# NodeSensor.net
KiCad netlist of a schematic drawn in Altium Designer
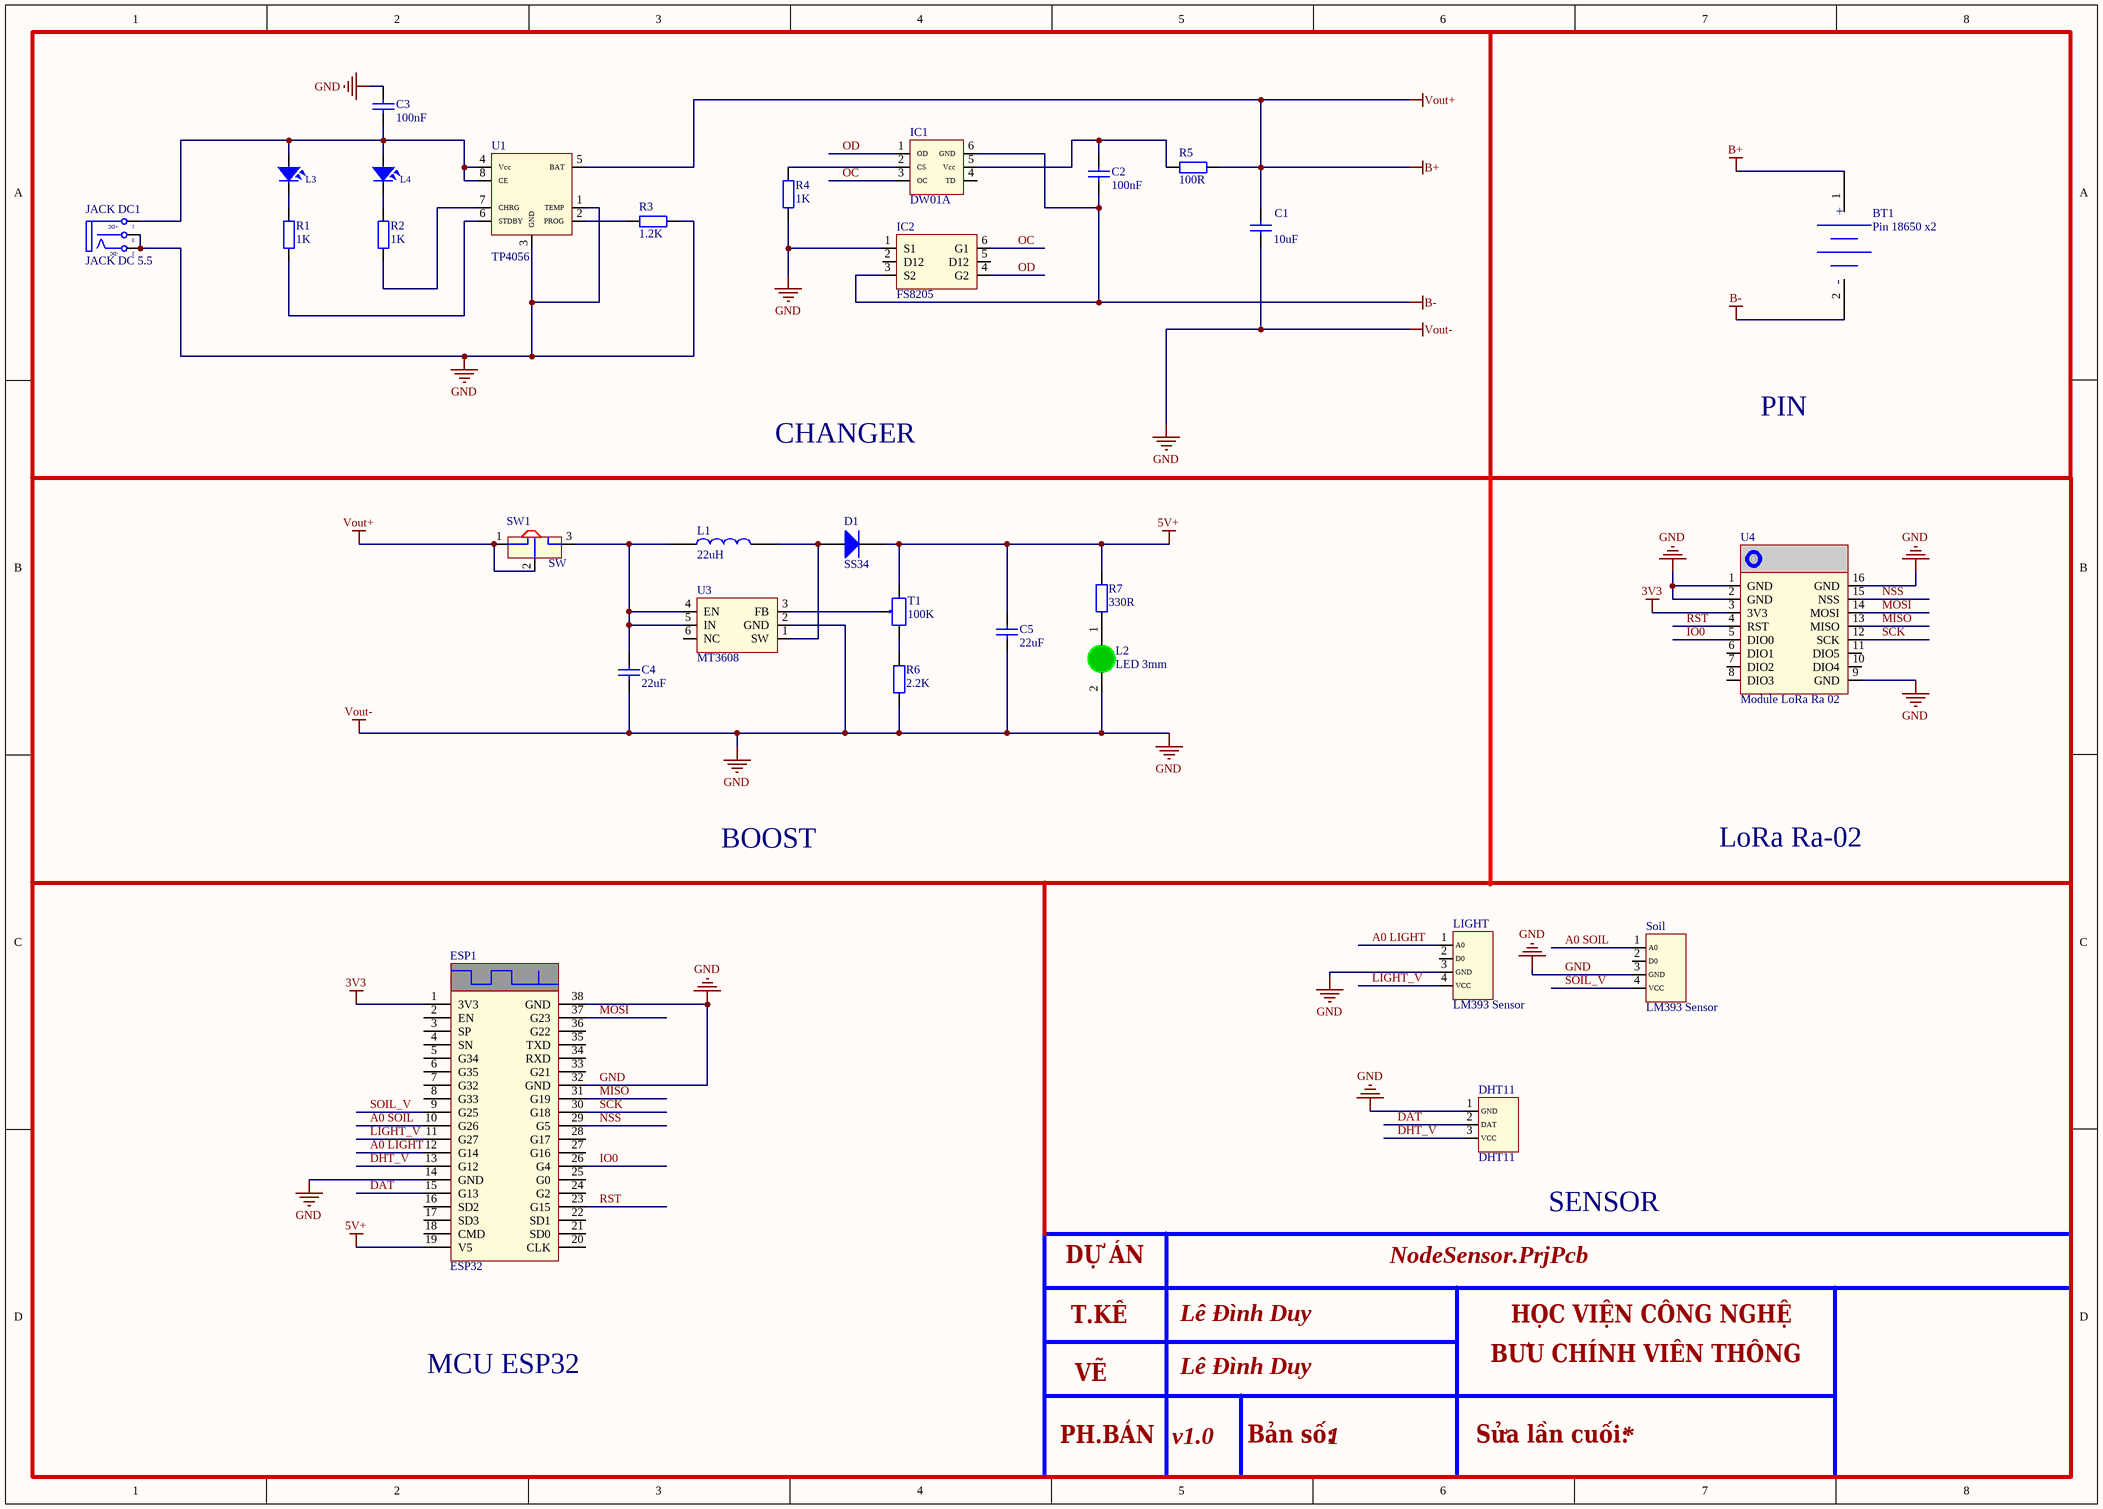
[diagram p0: NodeSensor.SchDoc]

(export (version "E")
  (design (tool "Eeschema 10.0.6"))
  (components
    (comp (ref "BT1")
      (value "Pin 18650 x2")
      (footprint "De Pin 18650 x2")
      (libsource (lib "Lib_byDuy") (part "De Pin 18650 x2"))
    )
    (comp (ref "C1")
      (value "10uF")
      (footprint "tu 0805")
      (description "Dán")
      (libsource (lib "Altium_Lib_by_KhueNguyenCreator") (part "Tu 0805 104 50V 10%"))
    )
    (comp (ref "C2")
      (value "100nF")
      (footprint "tu 0805")
      (description "Dán")
      (libsource (lib "Altium_Lib_by_KhueNguyenCreator") (part "Tu 0805 104 50V 10%"))
    )
    (comp (ref "C3")
      (value "100nF")
      (footprint "tu 0805")
      (description "Dán")
      (libsource (lib "Altium_Lib_by_KhueNguyenCreator") (part "Tu 0805 104 50V 10%"))
    )
    (comp (ref "C4")
      (value "22uF")
      (footprint "tu 1206")
      (description "Dán")
      (libsource (lib "Altium_Lib_by_KhueNguyenCreator") (part "Tu 1206 226 16V 20%"))
    )
    (comp (ref "C5")
      (value "22uF")
      (footprint "tu 1206")
      (description "Dán")
      (libsource (lib "Altium_Lib_by_KhueNguyenCreator") (part "Tu 1206 226 16V 20%"))
    )
    (comp (ref "D1")
      (value "SS34")
      (footprint "DIODE SMA")
      (description "Dán")
      (libsource (lib "Altium_Lib_by_KhueNguyenCreator") (part "Diode SS34 ( 1N5822 )"))
    )
    (comp (ref "DHT11")
      (value "DHT11")
      (footprint "DHT11 Module")
      (libsource (lib "Lib_byDuy") (part "DHT11 Module"))
    )
    (comp (ref "ESP1")
      (value "ESP32")
      (footprint "ESP32 DEVKIT 38Pin")
      (description "Board")
      (libsource (lib "Lib_byDuy") (part "ESP32 DEV KIT"))
    )
    (comp (ref "IC1") (value "DW01A") (footprint "DW01A") (libsource (lib "Lib_byDuy") (part "DW01A")))
    (comp (ref "IC2")
      (value "FS8205")
      (footprint "FS8205")
      (description "SOT23-6")
      (libsource (lib "Lib_byDuy") (part "FS8205"))
    )
    (comp (ref "JACK DC1")
      (value "JACK DC 5.5")
      (footprint "JACK DC 5.5")
      (libsource (lib "Altium_Lib_by_KhueNguyenCreator") (part "JACK DC 5.5"))
    )
    (comp (ref "L1")
      (value "22uH")
      (footprint "Cuon Cam 7x7x5")
      (description "Dán")
      (libsource (lib "Altium_Lib_by_KhueNguyenCreator") (part "CUON CAM 47uH SMD"))
    )
    (comp (ref "L2")
      (value "LED 3mm")
      (footprint "LED-3MM-GREEN")
      (description "Cắm")
      (libsource (lib "Altium_Lib_by_KhueNguyenCreator") (part "LED 3mm Xanh La"))
    )
    (comp (ref "L3")
      (value "LED SMD")
      (footprint "SM-LED-0805-Red")
      (libsource (lib "My library altium") (part "LED SMD 0805"))
    )
    (comp (ref "L4")
      (value "LED SMD")
      (footprint "SM-LED-0805-Red")
      (libsource (lib "My library altium") (part "LED SMD 0805"))
    )
    (comp (ref "LIGHT")
      (value "LM393 Sensor")
      (footprint "Soil /Light Sensor")
      (libsource (lib "Lib_byDuy") (part "Light/Soil sensor"))
    )
    (comp (ref "R1")
      (value "1K")
      (footprint "tro smd 0805")
      (description "Dán")
      (libsource (lib "Altium_Lib_by_KhueNguyenCreator") (part "Tro 0805 5% 1k"))
    )
    (comp (ref "R2")
      (value "1K")
      (footprint "tro smd 0805")
      (description "Dán")
      (libsource (lib "Altium_Lib_by_KhueNguyenCreator") (part "Tro 0805 5% 1k"))
    )
    (comp (ref "R3")
      (value "1.2K")
      (footprint "tro smd 0805")
      (description "Dán")
      (libsource (lib "Altium_Lib_by_KhueNguyenCreator") (part "Tro 0805 5% 1k"))
    )
    (comp (ref "R4")
      (value "1K")
      (footprint "tro smd 0805")
      (description "Dán")
      (libsource (lib "Altium_Lib_by_KhueNguyenCreator") (part "Tro 0805 5% 1k"))
    )
    (comp (ref "R5")
      (value "100R")
      (footprint "tro smd 0805")
      (description "Dán")
      (libsource (lib "Altium_Lib_by_KhueNguyenCreator") (part "Tro 0805 5% 1k"))
    )
    (comp (ref "R6")
      (value "2.2K")
      (footprint "tro smd 0805")
      (description "Dán")
      (libsource (lib "Altium_Lib_by_KhueNguyenCreator") (part "Tro 0805 5% 1k"))
    )
    (comp (ref "R7")
      (value "330R")
      (footprint "tro smd 0805")
      (description "Dán")
      (libsource (lib "Altium_Lib_by_KhueNguyenCreator") (part "Tro 0805 5% 1k"))
    )
    (comp (ref "Soil")
      (value "LM393 Sensor")
      (footprint "Soil /Light Sensor")
      (libsource (lib "Lib_byDuy") (part "Light/Soil sensor"))
    )
    (comp (ref "SW1")
      (value "SW")
      (footprint "CONG TAC GAT 3 PIN NGANG")
      (libsource (lib "Lib_byDuy") (part "CONG TAC GAT 3 PIN NGANG"))
    )
    (comp (ref "T1")
      (value "100K")
      (footprint "Bien Tro Vi Chinh Dung")
      (description "Cắm")
      (libsource (lib "Altium_Lib_by_KhueNguyenCreator") (part "Bien Tro Tinh Chinh 10K Dung"))
    )
    (comp (ref "U1") (value "TP4056") (footprint "TP4056") (libsource (lib "Lib_byDuy") (part "TP4056")))
    (comp (ref "U3")
      (value "MT3608")
      (footprint "MT3608")
      (description "SMD")
      (libsource (lib "Lib_byDuy") (part "MT3608"))
    )
    (comp (ref "U4")
      (value "Module LoRa Ra 02")
      (footprint "LoRa Ra 02 Module 2")
      (libsource (lib "Lib_byDuy") (part "LoRa Ra 02 Module 2"))
    )
  )
  (nets
    (net (code "1") (name "/A0 LIGHT") (class "Default")
      (node (ref "ESP1") (pin "12") (pinfunction "G14_12") (pintype "passive"))
      (node (ref "LIGHT") (pin "1") (pinfunction "A0_1") (pintype "passive"))
    )
    (net (code "2") (name "/A0 SOIL") (class "Default")
      (node (ref "ESP1") (pin "10") (pinfunction "G26_10") (pintype "passive"))
      (node (ref "Soil") (pin "1") (pinfunction "A0_1") (pintype "passive"))
    )
    (net (code "3") (name "/DAT") (class "Default")
      (node (ref "DHT11") (pin "2") (pinfunction "DAT_2") (pintype "passive"))
      (node (ref "ESP1") (pin "15") (pinfunction "G13_15") (pintype "passive"))
    )
    (net (code "4") (name "/DHT_V") (class "Default")
      (node (ref "DHT11") (pin "3") (pinfunction "VCC_3") (pintype "passive"))
      (node (ref "ESP1") (pin "13") (pinfunction "G12_13") (pintype "passive"))
    )
    (net (code "5") (name "/IO0") (class "Default")
      (node (ref "ESP1") (pin "26") (pinfunction "G4_26") (pintype "passive"))
      (node (ref "U4") (pin "5") (pinfunction "DIO0_5") (pintype "passive"))
    )
    (net (code "6") (name "/LIGHT_V") (class "Default")
      (node (ref "ESP1") (pin "11") (pinfunction "G27_11") (pintype "passive"))
      (node (ref "LIGHT") (pin "4") (pinfunction "VCC_4") (pintype "passive"))
    )
    (net (code "7") (name "/MISO") (class "Default")
      (node (ref "ESP1") (pin "31") (pinfunction "G19_31") (pintype "passive"))
      (node (ref "U4") (pin "13") (pinfunction "MISO_13") (pintype "passive"))
    )
    (net (code "8") (name "/MOSI") (class "Default")
      (node (ref "ESP1") (pin "37") (pinfunction "G23_37") (pintype "passive"))
      (node (ref "U4") (pin "14") (pinfunction "MOSI_14") (pintype "passive"))
    )
    (net (code "9") (name "/NSS") (class "Default")
      (node (ref "ESP1") (pin "29") (pinfunction "G5_29") (pintype "passive"))
      (node (ref "U4") (pin "15") (pinfunction "NSS_15") (pintype "passive"))
    )
    (net (code "10") (name "/OC") (class "Default")
      (node (ref "IC1") (pin "3") (pinfunction "OC_3") (pintype "passive"))
      (node (ref "IC2") (pin "6") (pinfunction "G1_6") (pintype "passive"))
    )
    (net (code "11") (name "/OD") (class "Default")
      (node (ref "IC1") (pin "1") (pinfunction "OD_1") (pintype "passive"))
      (node (ref "IC2") (pin "4") (pinfunction "G2_4") (pintype "passive"))
    )
    (net (code "12") (name "/RST") (class "Default")
      (node (ref "ESP1") (pin "23") (pinfunction "G15_23") (pintype "passive"))
      (node (ref "U4") (pin "4") (pinfunction "RST_4") (pintype "passive"))
    )
    (net (code "13") (name "/SCK") (class "Default")
      (node (ref "ESP1") (pin "30") (pinfunction "G18_30") (pintype "passive"))
      (node (ref "U4") (pin "12") (pinfunction "SCK_12") (pintype "passive"))
    )
    (net (code "14") (name "/SOIL_V") (class "Default")
      (node (ref "ESP1") (pin "9") (pinfunction "G25_9") (pintype "passive"))
      (node (ref "Soil") (pin "4") (pinfunction "VCC_4") (pintype "passive"))
    )
    (net (code "15") (name "3V3") (class "Default")
      (node (ref "ESP1") (pin "1") (pinfunction "3V3_1") (pintype "passive"))
      (node (ref "U4") (pin "3") (pinfunction "3V3_3") (pintype "passive"))
    )
    (net (code "16") (name "5V+") (class "Default")
      (node (ref "C5") (pin "1") (pinfunction "1_1") (pintype "passive"))
      (node (ref "D1") (pin "2") (pinfunction "K_2") (pintype "passive"))
      (node (ref "ESP1") (pin "19") (pinfunction "V5_19") (pintype "passive"))
      (node (ref "R7") (pin "1") (pinfunction "1_1") (pintype "passive"))
      (node (ref "T1") (pin "3") (pinfunction "3_3") (pintype "passive"))
    )
    (net (code "17") (name "B+") (class "Default")
      (node (ref "BT1") (pin "1") (pinfunction "+_1") (pintype "passive"))
      (node (ref "C1") (pin "1") (pinfunction "1_1") (pintype "passive"))
      (node (ref "R5") (pin "2") (pinfunction "2_2") (pintype "passive"))
      (node (ref "SW1") (pin "1") (pinfunction "1_1") (pintype "passive"))
      (node (ref "SW1") (pin "2") (pinfunction "2_2") (pintype "passive"))
      (node (ref "U1") (pin "5") (pinfunction "BAT_5") (pintype "passive"))
    )
    (net (code "18") (name "B-") (class "Default")
      (node (ref "BT1") (pin "2") (pinfunction "-_2") (pintype "passive"))
      (node (ref "C2") (pin "2") (pinfunction "2_2") (pintype "passive"))
      (node (ref "IC1") (pin "6") (pinfunction "GND_6") (pintype "passive"))
      (node (ref "IC2") (pin "3") (pinfunction "S2_3") (pintype "passive"))
    )
    (net (code "19") (name "GND") (class "Default")
      (node (ref "C1") (pin "2") (pinfunction "2_2") (pintype "passive"))
      (node (ref "C3") (pin "1") (pinfunction "1_1") (pintype "passive"))
      (node (ref "C4") (pin "2") (pinfunction "2_2") (pintype "passive"))
      (node (ref "C5") (pin "2") (pinfunction "2_2") (pintype "passive"))
      (node (ref "DHT11") (pin "1") (pinfunction "GND_1") (pintype "passive"))
      (node (ref "ESP1") (pin "14") (pinfunction "GND_14") (pintype "passive"))
      (node (ref "ESP1") (pin "32") (pinfunction "GND_32") (pintype "passive"))
      (node (ref "ESP1") (pin "38") (pinfunction "GND_38") (pintype "passive"))
      (node (ref "IC2") (pin "1") (pinfunction "S1_1") (pintype "passive"))
      (node (ref "JACK DC1") (pin "2") (pinfunction "TN_2") (pintype "passive"))
      (node (ref "JACK DC1") (pin "3") (pinfunction "S_3") (pintype "power_in"))
      (node (ref "L2") (pin "2") (pinfunction "K_2") (pintype "passive"))
      (node (ref "LIGHT") (pin "3") (pinfunction "GND_3") (pintype "passive"))
      (node (ref "R3") (pin "2") (pinfunction "2_2") (pintype "passive"))
      (node (ref "R4") (pin "2") (pinfunction "2_2") (pintype "passive"))
      (node (ref "R6") (pin "2") (pinfunction "2_2") (pintype "passive"))
      (node (ref "Soil") (pin "3") (pinfunction "GND_3") (pintype "passive"))
      (node (ref "U1") (pin "1") (pinfunction "TEMP_1") (pintype "passive"))
      (node (ref "U1") (pin "3") (pinfunction "GND_3") (pintype "passive"))
      (node (ref "U3") (pin "2") (pinfunction "GND_2") (pintype "passive"))
      (node (ref "U4") (pin "1") (pinfunction "GND_1") (pintype "passive"))
      (node (ref "U4") (pin "16") (pinfunction "GND_16") (pintype "passive"))
      (node (ref "U4") (pin "2") (pinfunction "GND_2") (pintype "passive"))
      (node (ref "U4") (pin "9") (pinfunction "GND_9") (pintype "passive"))
    )
    (net (code "20") (name "Net-(D1-A)") (class "Default")
      (node (ref "D1") (pin "1") (pinfunction "A_1") (pintype "passive"))
      (node (ref "L1") (pin "2") (pinfunction "2_2") (pintype "passive"))
      (node (ref "U3") (pin "1") (pinfunction "SW_1") (pintype "passive"))
    )
    (net (code "21") (name "Net-(IC1-CS)") (class "Default")
      (node (ref "IC1") (pin "2") (pinfunction "CS_2") (pintype "passive"))
      (node (ref "R4") (pin "1") (pinfunction "1_1") (pintype "passive"))
    )
    (net (code "22") (name "Net-(IC1-Vcc)") (class "Default")
      (node (ref "C2") (pin "1") (pinfunction "1_1") (pintype "passive"))
      (node (ref "IC1") (pin "5") (pinfunction "Vcc_5") (pintype "passive"))
      (node (ref "R5") (pin "1") (pinfunction "1_1") (pintype "passive"))
    )
    (net (code "23") (name "Net-(JACK DC1-T)") (class "Default")
      (node (ref "C3") (pin "2") (pinfunction "2_2") (pintype "passive"))
      (node (ref "JACK DC1") (pin "1") (pinfunction "T_1") (pintype "passive"))
      (node (ref "L3") (pin "1") (pinfunction "1_1") (pintype "passive"))
      (node (ref "L4") (pin "1") (pinfunction "1_1") (pintype "passive"))
      (node (ref "U1") (pin "4") (pinfunction "Vcc_4") (pintype "passive"))
      (node (ref "U1") (pin "8") (pinfunction "CE_8") (pintype "passive"))
    )
    (net (code "24") (name "Net-(L2-A)") (class "Default")
      (node (ref "L2") (pin "1") (pinfunction "A_1") (pintype "passive"))
      (node (ref "R7") (pin "2") (pinfunction "2_2") (pintype "passive"))
    )
    (net (code "25") (name "Net-(L3-Pad2)") (class "Default")
      (node (ref "L3") (pin "2") (pinfunction "2_2") (pintype "passive"))
      (node (ref "R1") (pin "1") (pinfunction "1_1") (pintype "passive"))
    )
    (net (code "26") (name "Net-(L4-Pad2)") (class "Default")
      (node (ref "L4") (pin "2") (pinfunction "2_2") (pintype "passive"))
      (node (ref "R2") (pin "1") (pinfunction "1_1") (pintype "passive"))
    )
    (net (code "27") (name "Net-(R6-Pad1)") (class "Default")
      (node (ref "R6") (pin "1") (pinfunction "1_1") (pintype "passive"))
      (node (ref "T1") (pin "1") (pinfunction "1_1") (pintype "passive"))
    )
    (net (code "28") (name "Net-(U1-CHRG)") (class "Default")
      (node (ref "R2") (pin "2") (pinfunction "2_2") (pintype "passive"))
      (node (ref "U1") (pin "7") (pinfunction "CHRG_7") (pintype "passive"))
    )
    (net (code "29") (name "Net-(U1-PROG)") (class "Default")
      (node (ref "R3") (pin "1") (pinfunction "1_1") (pintype "passive"))
      (node (ref "U1") (pin "2") (pinfunction "PROG_2") (pintype "passive"))
    )
    (net (code "30") (name "Net-(U1-STDBY)") (class "Default")
      (node (ref "R1") (pin "2") (pinfunction "2_2") (pintype "passive"))
      (node (ref "U1") (pin "6") (pinfunction "STDBY_6") (pintype "passive"))
    )
    (net (code "31") (name "Net-(U3-EN)") (class "Default")
      (node (ref "C4") (pin "1") (pinfunction "1_1") (pintype "passive"))
      (node (ref "L1") (pin "1") (pinfunction "1_1") (pintype "passive"))
      (node (ref "SW1") (pin "3") (pinfunction "3_3") (pintype "passive"))
      (node (ref "U3") (pin "4") (pinfunction "EN_4") (pintype "passive"))
      (node (ref "U3") (pin "5") (pinfunction "IN_5") (pintype "passive"))
    )
    (net (code "32") (name "Net-(U3-FB)") (class "Default")
      (node (ref "T1") (pin "2") (pinfunction "2_2") (pintype "passive"))
      (node (ref "U3") (pin "3") (pinfunction "FB_3") (pintype "passive"))
    )
    (net (code "33") (name "unconnected-(ESP1-CLK-Pad20)") (class "Default")
      (node (ref "ESP1") (pin "20") (pinfunction "CLK_20") (pintype "passive"))
    )
    (net (code "34") (name "unconnected-(ESP1-CMD-Pad18)") (class "Default")
      (node (ref "ESP1") (pin "18") (pinfunction "CMD_18") (pintype "passive"))
    )
    (net (code "35") (name "unconnected-(ESP1-EN-Pad2)") (class "Default")
      (node (ref "ESP1") (pin "2") (pinfunction "EN_2") (pintype "passive"))
    )
    (net (code "36") (name "unconnected-(ESP1-G0-Pad25)") (class "Default")
      (node (ref "ESP1") (pin "25") (pinfunction "G0_25") (pintype "passive"))
    )
    (net (code "37") (name "unconnected-(ESP1-G2-Pad24)") (class "Default")
      (node (ref "ESP1") (pin "24") (pinfunction "G2_24") (pintype "passive"))
    )
    (net (code "38") (name "unconnected-(ESP1-G16-Pad27)") (class "Default")
      (node (ref "ESP1") (pin "27") (pinfunction "G16_27") (pintype "passive"))
    )
    (net (code "39") (name "unconnected-(ESP1-G17-Pad28)") (class "Default")
      (node (ref "ESP1") (pin "28") (pinfunction "G17_28") (pintype "passive"))
    )
    (net (code "40") (name "unconnected-(ESP1-G21-Pad33)") (class "Default")
      (node (ref "ESP1") (pin "33") (pinfunction "G21_33") (pintype "passive"))
    )
    (net (code "41") (name "unconnected-(ESP1-G22-Pad36)") (class "Default")
      (node (ref "ESP1") (pin "36") (pinfunction "G22_36") (pintype "passive"))
    )
    (net (code "42") (name "unconnected-(ESP1-G32-Pad7)") (class "Default")
      (node (ref "ESP1") (pin "7") (pinfunction "G32_7") (pintype "passive"))
    )
    (net (code "43") (name "unconnected-(ESP1-G33-Pad8)") (class "Default")
      (node (ref "ESP1") (pin "8") (pinfunction "G33_8") (pintype "passive"))
    )
    (net (code "44") (name "unconnected-(ESP1-G34-Pad5)") (class "Default")
      (node (ref "ESP1") (pin "5") (pinfunction "G34_5") (pintype "passive"))
    )
    (net (code "45") (name "unconnected-(ESP1-G35-Pad6)") (class "Default")
      (node (ref "ESP1") (pin "6") (pinfunction "G35_6") (pintype "passive"))
    )
    (net (code "46") (name "unconnected-(ESP1-RXD-Pad34)") (class "Default")
      (node (ref "ESP1") (pin "34") (pinfunction "RXD_34") (pintype "passive"))
    )
    (net (code "47") (name "unconnected-(ESP1-SD0-Pad21)") (class "Default")
      (node (ref "ESP1") (pin "21") (pinfunction "SD0_21") (pintype "passive"))
    )
    (net (code "48") (name "unconnected-(ESP1-SD1-Pad22)") (class "Default")
      (node (ref "ESP1") (pin "22") (pinfunction "SD1_22") (pintype "passive"))
    )
    (net (code "49") (name "unconnected-(ESP1-SD2-Pad16)") (class "Default")
      (node (ref "ESP1") (pin "16") (pinfunction "SD2_16") (pintype "passive"))
    )
    (net (code "50") (name "unconnected-(ESP1-SD3-Pad17)") (class "Default")
      (node (ref "ESP1") (pin "17") (pinfunction "SD3_17") (pintype "passive"))
    )
    (net (code "51") (name "unconnected-(ESP1-SN-Pad4)") (class "Default")
      (node (ref "ESP1") (pin "4") (pinfunction "SN_4") (pintype "passive"))
    )
    (net (code "52") (name "unconnected-(ESP1-SP-Pad3)") (class "Default")
      (node (ref "ESP1") (pin "3") (pinfunction "SP_3") (pintype "passive"))
    )
    (net (code "53") (name "unconnected-(ESP1-TXD-Pad35)") (class "Default")
      (node (ref "ESP1") (pin "35") (pinfunction "TXD_35") (pintype "passive"))
    )
    (net (code "54") (name "unconnected-(IC1-TD-Pad4)") (class "Default")
      (node (ref "IC1") (pin "4") (pinfunction "TD_4") (pintype "passive"))
    )
    (net (code "55") (name "unconnected-(IC2-D12-Pad2)") (class "Default")
      (node (ref "IC2") (pin "2") (pinfunction "D12_2") (pintype "passive"))
    )
    (net (code "56") (name "unconnected-(IC2-D12-Pad5)") (class "Default")
      (node (ref "IC2") (pin "5") (pinfunction "D12_5") (pintype "passive"))
    )
    (net (code "57") (name "unconnected-(LIGHT-D0-Pad2)") (class "Default")
      (node (ref "LIGHT") (pin "2") (pinfunction "D0_2") (pintype "passive"))
    )
    (net (code "58") (name "unconnected-(Soil-D0-Pad2)") (class "Default")
      (node (ref "Soil") (pin "2") (pinfunction "D0_2") (pintype "passive"))
    )
    (net (code "59") (name "unconnected-(U3-NC-Pad6)") (class "Default")
      (node (ref "U3") (pin "6") (pinfunction "NC_6") (pintype "passive"))
    )
    (net (code "60") (name "unconnected-(U4-DIO1-Pad6)") (class "Default")
      (node (ref "U4") (pin "6") (pinfunction "DIO1_6") (pintype "passive"))
    )
    (net (code "61") (name "unconnected-(U4-DIO2-Pad7)") (class "Default")
      (node (ref "U4") (pin "7") (pinfunction "DIO2_7") (pintype "passive"))
    )
    (net (code "62") (name "unconnected-(U4-DIO3-Pad8)") (class "Default")
      (node (ref "U4") (pin "8") (pinfunction "DIO3_8") (pintype "passive"))
    )
    (net (code "63") (name "unconnected-(U4-DIO4-Pad10)") (class "Default")
      (node (ref "U4") (pin "10") (pinfunction "DIO4_10") (pintype "passive"))
    )
    (net (code "64") (name "unconnected-(U4-DIO5-Pad11)") (class "Default")
      (node (ref "U4") (pin "11") (pinfunction "DIO5_11") (pintype "passive"))
    )
  )
)
